# untitled.net
KiCad netlist of a schematic drawn in EAGLE
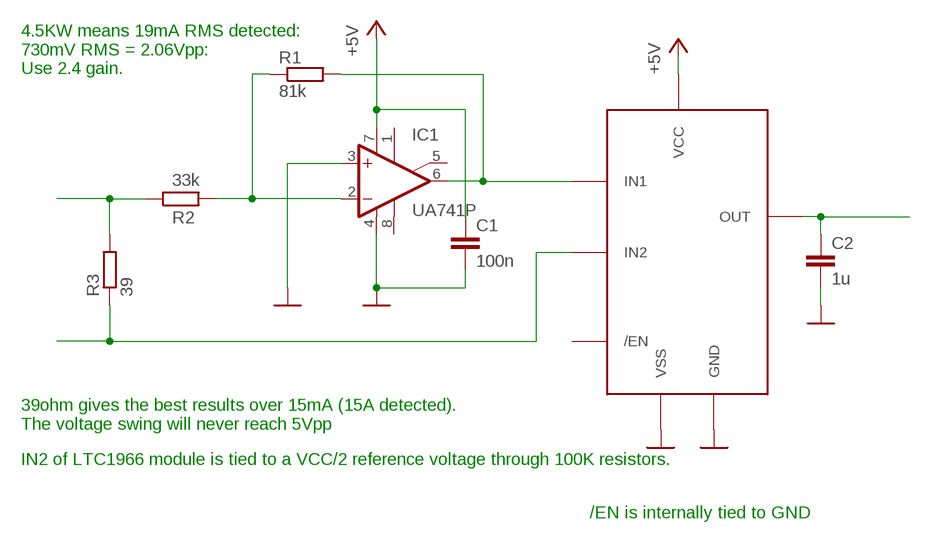
[diagram p0: schematic, sheet 1]

(export (version "E")
  (design (tool "Eeschema 10.0.6"))
  (components
    (comp (ref "C1")
      (value "100n")
      (footprint "eagle-import:C025-025X050")
      (libsource (lib "eagle-import") (part "C-EU025-025X050"))
    )
    (comp (ref "C2")
      (value "1u")
      (footprint "eagle-import:C025-025X050")
      (libsource (lib "eagle-import") (part "C-EU025-025X050"))
    )
    (comp (ref "IC1")
      (value "UA741P")
      (footprint "eagle-import:DIL08")
      (fields (field (name "SPICEPREFIX") "X"))
      (libsource (lib "eagle-import") (part "741PUA"))
    )
    (comp (ref "R1")
      (value "81k")
      (footprint "eagle-import:0207_10")
      (libsource (lib "eagle-import") (part "R-EU_0207/10"))
    )
    (comp (ref "R2")
      (value "33k")
      (footprint "eagle-import:0207_10")
      (libsource (lib "eagle-import") (part "R-EU_0207/10"))
    )
    (comp (ref "R3")
      (value "39")
      (footprint "eagle-import:0207_10")
      (libsource (lib "eagle-import") (part "R-EU_0207/10"))
    )
    (comp (ref "U$1")
      (value "LTC1966_MODULE")
      (footprint "eagle-import:LTC1966_MODULE")
      (libsource (lib "eagle-import") (part "LTC1966_MODULE"))
    )
  )
  (nets
    (net (code "1") (name "+5V") (class "Default")
      (node (ref "C1") (pin "1") (pinfunction "1_1") (pintype "passive"))
      (node (ref "IC1") (pin "7") (pinfunction "V+_7") (pintype "power_in"))
      (node (ref "U$1") (pin "P$1") (pinfunction "VCC_P$1") (pintype "bidirectional"))
    )
    (net (code "2") (name "GND") (class "Default")
      (node (ref "C1") (pin "2") (pinfunction "2_2") (pintype "passive"))
      (node (ref "C2") (pin "2") (pinfunction "2_2") (pintype "passive"))
      (node (ref "IC1") (pin "3") (pinfunction "+IN_3") (pintype "input"))
      (node (ref "IC1") (pin "4") (pinfunction "V-_4") (pintype "power_in"))
      (node (ref "U$1") (pin "P$2") (pinfunction "GND_P$2") (pintype "bidirectional"))
      (node (ref "U$1") (pin "P$3") (pinfunction "VSS_P$3") (pintype "bidirectional"))
    )
    (net (code "3") (name "Net-(IC1--IN)") (class "Default")
      (node (ref "IC1") (pin "2") (pinfunction "-IN_2") (pintype "input"))
      (node (ref "R1") (pin "1") (pinfunction "1_1") (pintype "passive"))
      (node (ref "R2") (pin "2") (pinfunction "2_2") (pintype "passive"))
    )
    (net (code "4") (name "Net-(IC1-OUT)") (class "Default")
      (node (ref "IC1") (pin "6") (pinfunction "OUT_6") (pintype "output"))
      (node (ref "R1") (pin "2") (pinfunction "2_2") (pintype "passive"))
      (node (ref "U$1") (pin "P$4") (pinfunction "IN1_P$4") (pintype "bidirectional"))
    )
    (net (code "5") (name "Net-(R2-Pad1)") (class "Default")
      (node (ref "R2") (pin "1") (pinfunction "1_1") (pintype "passive"))
      (node (ref "R3") (pin "2") (pinfunction "2_2") (pintype "passive"))
    )
    (net (code "6") (name "Net-(U$1-IN2)") (class "Default")
      (node (ref "R3") (pin "1") (pinfunction "1_1") (pintype "passive"))
      (node (ref "U$1") (pin "P$5") (pinfunction "IN2_P$5") (pintype "bidirectional"))
    )
    (net (code "7") (name "Net-(U$1-OUT)") (class "Default")
      (node (ref "C2") (pin "1") (pinfunction "1_1") (pintype "passive"))
      (node (ref "U$1") (pin "P$6") (pinfunction "OUT_P$6") (pintype "bidirectional"))
    )
    (net (code "8") (name "unconnected-(IC1-ON1-Pad1)") (class "Default")
      (node (ref "IC1") (pin "1") (pinfunction "ON1_1") (pintype "passive"))
    )
    (net (code "9") (name "unconnected-(IC1-ON2-Pad5)") (class "Default")
      (node (ref "IC1") (pin "5") (pinfunction "ON2_5") (pintype "passive"))
    )
    (net (code "10") (name "unconnected-(IC1-OPT-Pad8)") (class "Default")
      (node (ref "IC1") (pin "8") (pinfunction "OPT_8") (pintype "passive"))
    )
    (net (code "11") (name "unconnected-(U$1-{slash}EN-PadP$7)") (class "Default")
      (node (ref "U$1") (pin "P$7") (pinfunction "/EN_P$7") (pintype "bidirectional"))
    )
  )
)
